# MC21R01_uC_Power.net
KiCad netlist of a schematic drawn in Altium Designer
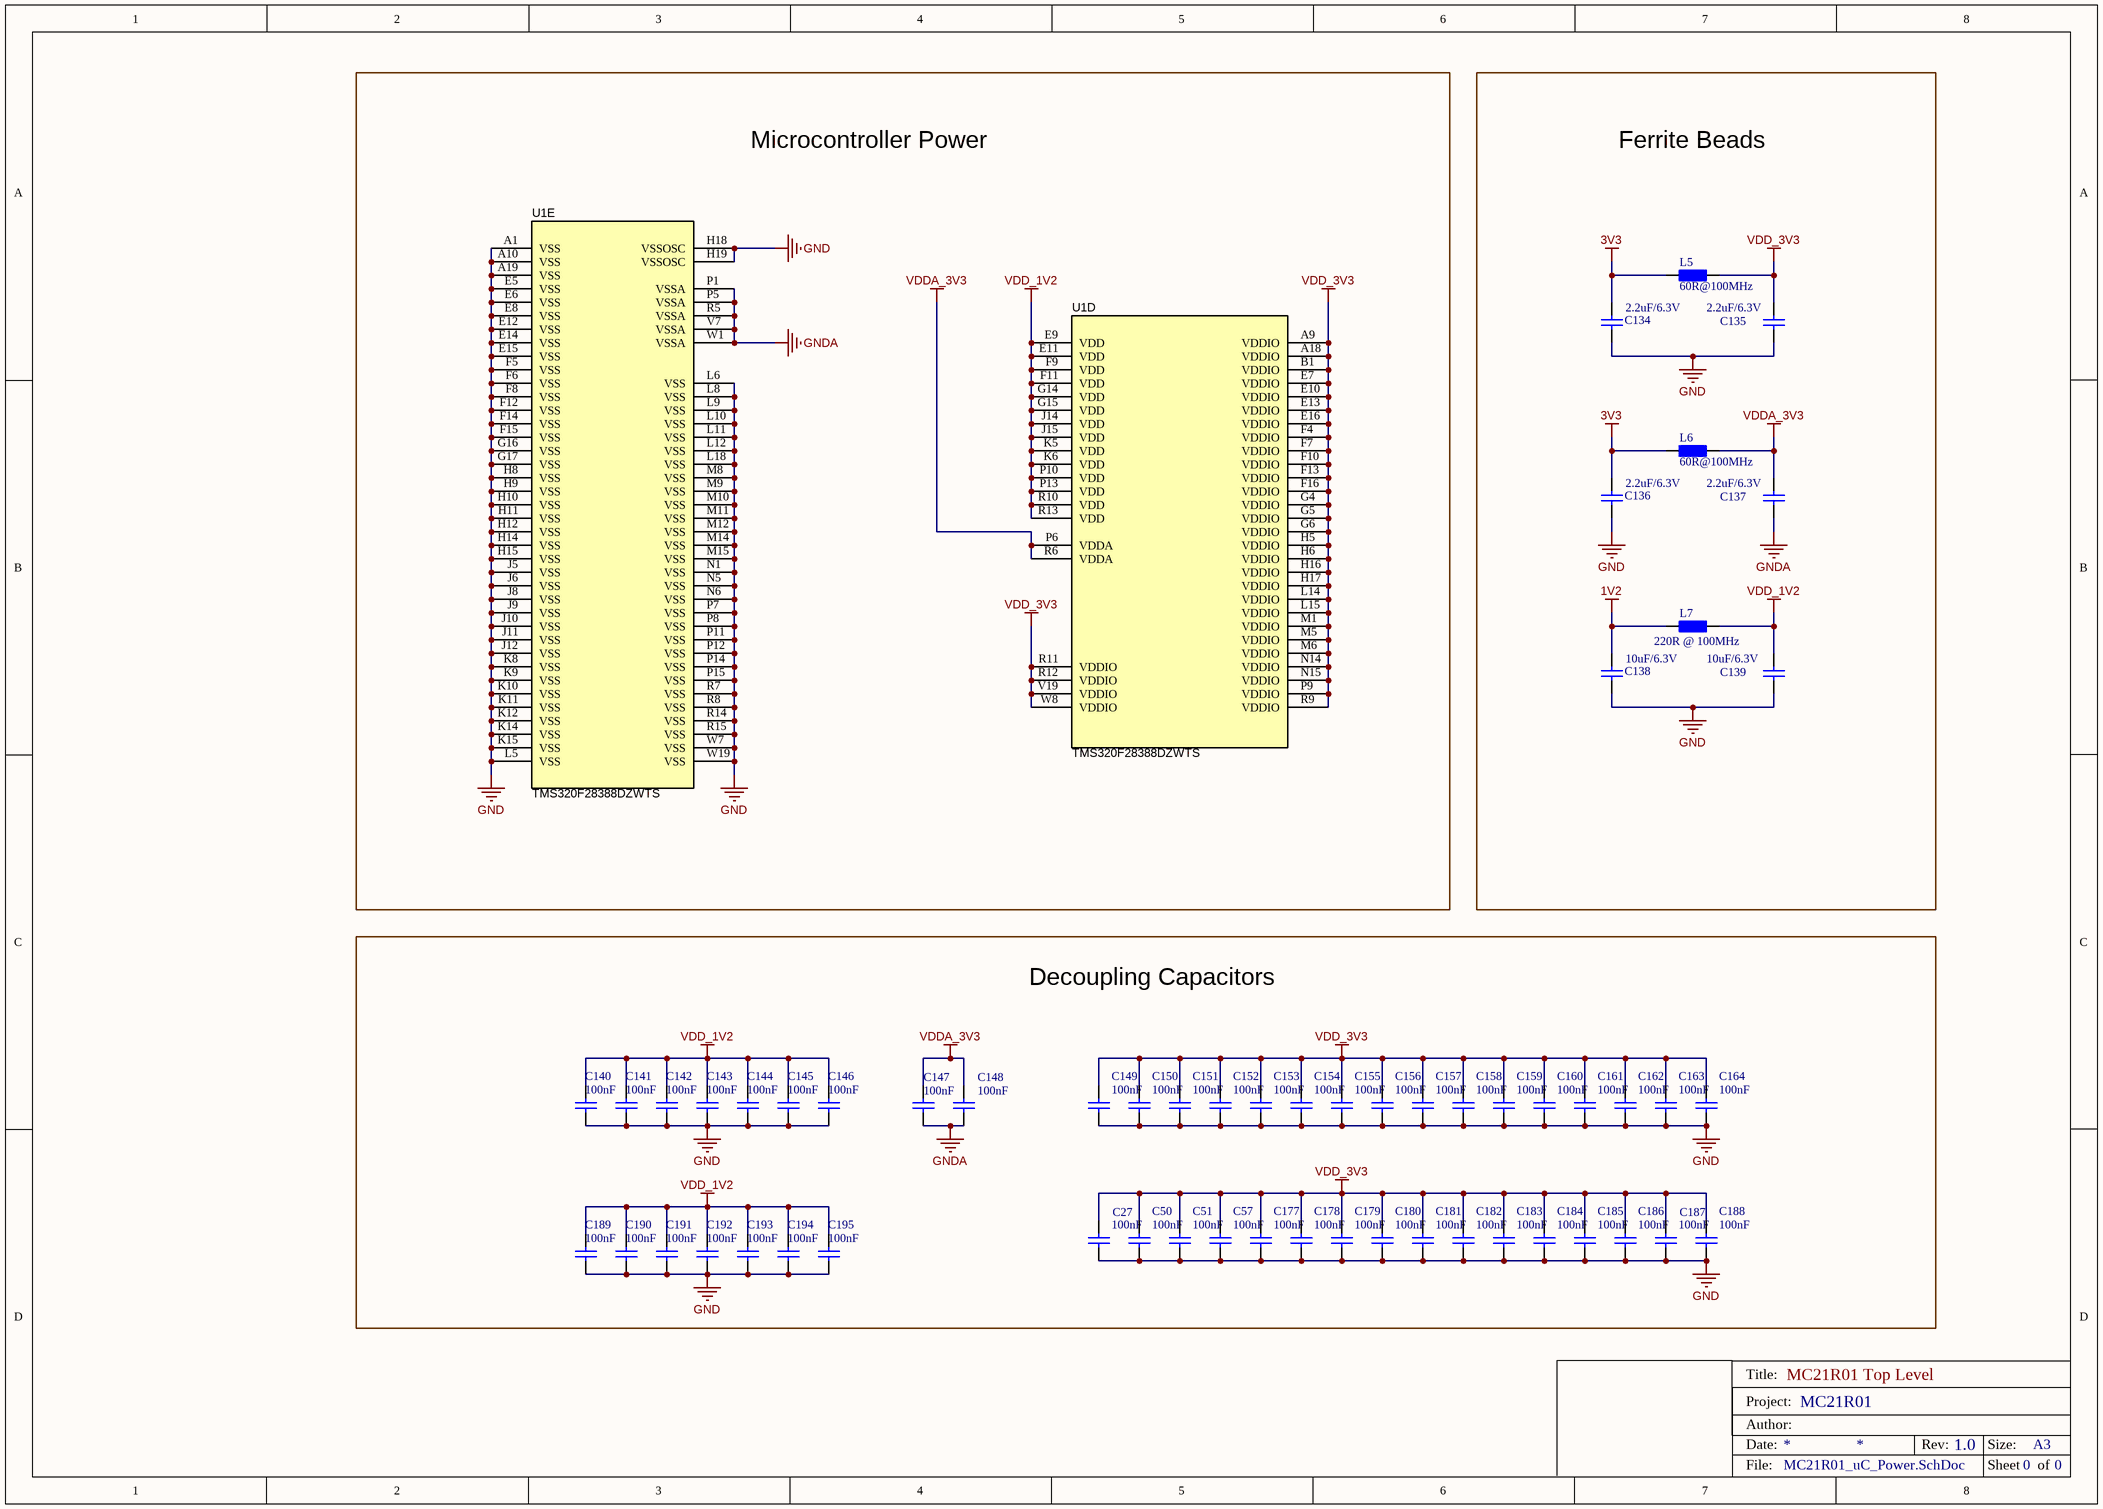
[diagram p0: MC21R01_uC_Power.SchDoc]

(export (version "E")
  (design (tool "Eeschema 10.0.6"))
  (components
    (comp (ref "C27")
      (value "100nF")
      (footprint "CAPC0603X03N")
      (description "100nF/25V 0201 10% Tolerance X6S Multilayer Ceramic Chip Capacitor")
      (fields (field (name "TOLERANCE") "10%") (field (name "Comment") "100nF/25V 0201 10% X6S"))
      (libsource (lib "Wandercraft") (part "STD_CAP_2PIN_NPOL"))
    )
    (comp (ref "C50")
      (value "100nF")
      (footprint "CAPC0603X03N")
      (description "100nF/25V 0201 10% Tolerance X6S Multilayer Ceramic Chip Capacitor")
      (fields (field (name "TOLERANCE") "10%") (field (name "Comment") "100nF/25V 0201 10% X6S"))
      (libsource (lib "Wandercraft") (part "STD_CAP_2PIN_NPOL"))
    )
    (comp (ref "C51")
      (value "100nF")
      (footprint "CAPC0603X03N")
      (description "100nF/25V 0201 10% Tolerance X6S Multilayer Ceramic Chip Capacitor")
      (fields (field (name "TOLERANCE") "10%") (field (name "Comment") "100nF/25V 0201 10% X6S"))
      (libsource (lib "Wandercraft") (part "STD_CAP_2PIN_NPOL"))
    )
    (comp (ref "C57")
      (value "100nF")
      (footprint "CAPC0603X03N")
      (description "100nF/25V 0201 10% Tolerance X6S Multilayer Ceramic Chip Capacitor")
      (fields (field (name "TOLERANCE") "10%") (field (name "Comment") "100nF/25V 0201 10% X6S"))
      (libsource (lib "Wandercraft") (part "STD_CAP_2PIN_NPOL"))
    )
    (comp (ref "C134")
      (value "2.2uF/6.3V")
      (footprint "PAL_Capacitors:0402 SMD Capacitor")
      (description "2.2uF/6.3V 0402 10% Tolerance X5R Multilayer Ceramic Chip Capacitor")
      (fields (field (name "Comment") "2.2uF/6.3V 0402 10% X5R"))
      (libsource (lib "PAL_Capacitors") (part "2.2uF/6.3V 0402 10% X5R_1"))
    )
    (comp (ref "C135")
      (value "2.2uF/6.3V")
      (footprint "PAL_Capacitors:0402 SMD Capacitor")
      (description "2.2uF/6.3V 0402 10% Tolerance X5R Multilayer Ceramic Chip Capacitor")
      (fields (field (name "Comment") "2.2uF/6.3V 0402 10% X5R"))
      (libsource (lib "PAL_Capacitors") (part "2.2uF/6.3V 0402 10% X5R_1"))
    )
    (comp (ref "C136")
      (value "2.2uF/6.3V")
      (footprint "PAL_Capacitors:0402 SMD Capacitor")
      (description "2.2uF/6.3V 0402 10% Tolerance X5R Multilayer Ceramic Chip Capacitor")
      (fields (field (name "Comment") "2.2uF/6.3V 0402 10% X5R"))
      (libsource (lib "PAL_Capacitors") (part "2.2uF/6.3V 0402 10% X5R_1"))
    )
    (comp (ref "C137")
      (value "2.2uF/6.3V")
      (footprint "PAL_Capacitors:0402 SMD Capacitor")
      (description "2.2uF/6.3V 0402 10% Tolerance X5R Multilayer Ceramic Chip Capacitor")
      (fields (field (name "Comment") "2.2uF/6.3V 0402 10% X5R"))
      (libsource (lib "PAL_Capacitors") (part "2.2uF/6.3V 0402 10% X5R_1"))
    )
    (comp (ref "C138")
      (value "10uF/6.3V")
      (footprint "PAL_Capacitors:0402 SMD Capacitor")
      (description "10uF/6.3V 0402 20% Tolerance X5R Multilayer Ceramic Chip Capacitor")
      (fields (field (name "Comment") "10uF/6.3V 0402 20% X5R"))
      (libsource (lib "PAL_Capacitors") (part "10uF/6.3V 0402 20% X5R"))
    )
    (comp (ref "C139")
      (value "10uF/6.3V")
      (footprint "PAL_Capacitors:0402 SMD Capacitor")
      (description "10uF/6.3V 0402 20% Tolerance X5R Multilayer Ceramic Chip Capacitor")
      (fields (field (name "Comment") "10uF/6.3V 0402 20% X5R"))
      (libsource (lib "PAL_Capacitors") (part "10uF/6.3V 0402 20% X5R"))
    )
    (comp (ref "C140")
      (value "100nF")
      (footprint "CAPC0603X03N")
      (description "100nF/25V 0201 10% Tolerance X6S Multilayer Ceramic Chip Capacitor")
      (fields (field (name "TOLERANCE") "10%") (field (name "Comment") "100nF/25V 0201 10% X6S"))
      (libsource (lib "Wandercraft") (part "STD_CAP_2PIN_NPOL"))
    )
    (comp (ref "C141")
      (value "100nF")
      (footprint "CAPC0603X03N")
      (description "100nF/25V 0201 10% Tolerance X6S Multilayer Ceramic Chip Capacitor")
      (fields (field (name "TOLERANCE") "10%") (field (name "Comment") "100nF/25V 0201 10% X6S"))
      (libsource (lib "Wandercraft") (part "STD_CAP_2PIN_NPOL"))
    )
    (comp (ref "C142")
      (value "100nF")
      (footprint "CAPC0603X03N")
      (description "100nF/25V 0201 10% Tolerance X6S Multilayer Ceramic Chip Capacitor")
      (fields (field (name "TOLERANCE") "10%") (field (name "Comment") "100nF/25V 0201 10% X6S"))
      (libsource (lib "Wandercraft") (part "STD_CAP_2PIN_NPOL"))
    )
    (comp (ref "C143")
      (value "100nF")
      (footprint "CAPC0603X03N")
      (description "100nF/25V 0201 10% Tolerance X6S Multilayer Ceramic Chip Capacitor")
      (fields (field (name "TOLERANCE") "10%") (field (name "Comment") "100nF/25V 0201 10% X6S"))
      (libsource (lib "Wandercraft") (part "STD_CAP_2PIN_NPOL"))
    )
    (comp (ref "C144")
      (value "100nF")
      (footprint "CAPC0603X03N")
      (description "100nF/25V 0201 10% Tolerance X6S Multilayer Ceramic Chip Capacitor")
      (fields (field (name "TOLERANCE") "10%") (field (name "Comment") "100nF/25V 0201 10% X6S"))
      (libsource (lib "Wandercraft") (part "STD_CAP_2PIN_NPOL"))
    )
    (comp (ref "C145")
      (value "100nF")
      (footprint "CAPC0603X03N")
      (description "100nF/25V 0201 10% Tolerance X6S Multilayer Ceramic Chip Capacitor")
      (fields (field (name "TOLERANCE") "10%") (field (name "Comment") "100nF/25V 0201 10% X6S"))
      (libsource (lib "Wandercraft") (part "STD_CAP_2PIN_NPOL"))
    )
    (comp (ref "C146")
      (value "100nF")
      (footprint "CAPC0603X03N")
      (description "100nF/25V 0201 10% Tolerance X6S Multilayer Ceramic Chip Capacitor")
      (fields (field (name "TOLERANCE") "10%") (field (name "Comment") "100nF/25V 0201 10% X6S"))
      (libsource (lib "Wandercraft") (part "STD_CAP_2PIN_NPOL"))
    )
    (comp (ref "C147")
      (value "100nF")
      (footprint "CAPC0603X03N")
      (description "100nF/25V 0201 10% Tolerance X6S Multilayer Ceramic Chip Capacitor")
      (fields (field (name "TOLERANCE") "10%") (field (name "Comment") "100nF/25V 0201 10% X6S"))
      (libsource (lib "Wandercraft") (part "STD_CAP_2PIN_NPOL"))
    )
    (comp (ref "C148")
      (value "100nF")
      (footprint "CAPC0603X03N")
      (description "100nF/25V 0201 10% Tolerance X6S Multilayer Ceramic Chip Capacitor")
      (fields (field (name "TOLERANCE") "10%") (field (name "Comment") "100nF/25V 0201 10% X6S"))
      (libsource (lib "Wandercraft") (part "STD_CAP_2PIN_NPOL"))
    )
    (comp (ref "C149")
      (value "100nF")
      (footprint "CAPC0603X03N")
      (description "100nF/25V 0201 10% Tolerance X6S Multilayer Ceramic Chip Capacitor")
      (fields (field (name "TOLERANCE") "10%") (field (name "Comment") "100nF/25V 0201 10% X6S"))
      (libsource (lib "Wandercraft") (part "STD_CAP_2PIN_NPOL"))
    )
    (comp (ref "C150")
      (value "100nF")
      (footprint "CAPC0603X03N")
      (description "100nF/25V 0201 10% Tolerance X6S Multilayer Ceramic Chip Capacitor")
      (fields (field (name "TOLERANCE") "10%") (field (name "Comment") "100nF/25V 0201 10% X6S"))
      (libsource (lib "Wandercraft") (part "STD_CAP_2PIN_NPOL"))
    )
    (comp (ref "C151")
      (value "100nF")
      (footprint "CAPC0603X03N")
      (description "100nF/25V 0201 10% Tolerance X6S Multilayer Ceramic Chip Capacitor")
      (fields (field (name "TOLERANCE") "10%") (field (name "Comment") "100nF/25V 0201 10% X6S"))
      (libsource (lib "Wandercraft") (part "STD_CAP_2PIN_NPOL"))
    )
    (comp (ref "C152")
      (value "100nF")
      (footprint "CAPC0603X03N")
      (description "100nF/25V 0201 10% Tolerance X6S Multilayer Ceramic Chip Capacitor")
      (fields (field (name "TOLERANCE") "10%") (field (name "Comment") "100nF/25V 0201 10% X6S"))
      (libsource (lib "Wandercraft") (part "STD_CAP_2PIN_NPOL"))
    )
    (comp (ref "C153")
      (value "100nF")
      (footprint "CAPC0603X03N")
      (description "100nF/25V 0201 10% Tolerance X6S Multilayer Ceramic Chip Capacitor")
      (fields (field (name "TOLERANCE") "10%") (field (name "Comment") "100nF/25V 0201 10% X6S"))
      (libsource (lib "Wandercraft") (part "STD_CAP_2PIN_NPOL"))
    )
    (comp (ref "C154")
      (value "100nF")
      (footprint "CAPC0603X03N")
      (description "100nF/25V 0201 10% Tolerance X6S Multilayer Ceramic Chip Capacitor")
      (fields (field (name "TOLERANCE") "10%") (field (name "Comment") "100nF/25V 0201 10% X6S"))
      (libsource (lib "Wandercraft") (part "STD_CAP_2PIN_NPOL"))
    )
    (comp (ref "C155")
      (value "100nF")
      (footprint "CAPC0603X03N")
      (description "100nF/25V 0201 10% Tolerance X6S Multilayer Ceramic Chip Capacitor")
      (fields (field (name "TOLERANCE") "10%") (field (name "Comment") "100nF/25V 0201 10% X6S"))
      (libsource (lib "Wandercraft") (part "STD_CAP_2PIN_NPOL"))
    )
    (comp (ref "C156")
      (value "100nF")
      (footprint "CAPC0603X03N")
      (description "100nF/25V 0201 10% Tolerance X6S Multilayer Ceramic Chip Capacitor")
      (fields (field (name "TOLERANCE") "10%") (field (name "Comment") "100nF/25V 0201 10% X6S"))
      (libsource (lib "Wandercraft") (part "STD_CAP_2PIN_NPOL"))
    )
    (comp (ref "C157")
      (value "100nF")
      (footprint "CAPC0603X03N")
      (description "100nF/25V 0201 10% Tolerance X6S Multilayer Ceramic Chip Capacitor")
      (fields (field (name "TOLERANCE") "10%") (field (name "Comment") "100nF/25V 0201 10% X6S"))
      (libsource (lib "Wandercraft") (part "STD_CAP_2PIN_NPOL"))
    )
    (comp (ref "C158")
      (value "100nF")
      (footprint "CAPC0603X03N")
      (description "100nF/25V 0201 10% Tolerance X6S Multilayer Ceramic Chip Capacitor")
      (fields (field (name "TOLERANCE") "10%") (field (name "Comment") "100nF/25V 0201 10% X6S"))
      (libsource (lib "Wandercraft") (part "STD_CAP_2PIN_NPOL"))
    )
    (comp (ref "C159")
      (value "100nF")
      (footprint "CAPC0603X03N")
      (description "100nF/25V 0201 10% Tolerance X6S Multilayer Ceramic Chip Capacitor")
      (fields (field (name "TOLERANCE") "10%") (field (name "Comment") "100nF/25V 0201 10% X6S"))
      (libsource (lib "Wandercraft") (part "STD_CAP_2PIN_NPOL"))
    )
    (comp (ref "C160")
      (value "100nF")
      (footprint "CAPC0603X03N")
      (description "100nF/25V 0201 10% Tolerance X6S Multilayer Ceramic Chip Capacitor")
      (fields (field (name "TOLERANCE") "10%") (field (name "Comment") "100nF/25V 0201 10% X6S"))
      (libsource (lib "Wandercraft") (part "STD_CAP_2PIN_NPOL"))
    )
    (comp (ref "C161")
      (value "100nF")
      (footprint "CAPC0603X03N")
      (description "100nF/25V 0201 10% Tolerance X6S Multilayer Ceramic Chip Capacitor")
      (fields (field (name "TOLERANCE") "10%") (field (name "Comment") "100nF/25V 0201 10% X6S"))
      (libsource (lib "Wandercraft") (part "STD_CAP_2PIN_NPOL"))
    )
    (comp (ref "C162")
      (value "100nF")
      (footprint "CAPC0603X03N")
      (description "100nF/25V 0201 10% Tolerance X6S Multilayer Ceramic Chip Capacitor")
      (fields (field (name "TOLERANCE") "10%") (field (name "Comment") "100nF/25V 0201 10% X6S"))
      (libsource (lib "Wandercraft") (part "STD_CAP_2PIN_NPOL"))
    )
    (comp (ref "C163")
      (value "100nF")
      (footprint "CAPC0603X03N")
      (description "100nF/25V 0201 10% Tolerance X6S Multilayer Ceramic Chip Capacitor")
      (fields (field (name "TOLERANCE") "10%") (field (name "Comment") "100nF/25V 0201 10% X6S"))
      (libsource (lib "Wandercraft") (part "STD_CAP_2PIN_NPOL"))
    )
    (comp (ref "C164")
      (value "100nF")
      (footprint "CAPC0603X03N")
      (description "100nF/25V 0201 10% Tolerance X6S Multilayer Ceramic Chip Capacitor")
      (fields (field (name "TOLERANCE") "10%") (field (name "Comment") "100nF/25V 0201 10% X6S"))
      (libsource (lib "Wandercraft") (part "STD_CAP_2PIN_NPOL"))
    )
    (comp (ref "C177")
      (value "100nF")
      (footprint "CAPC0603X03N")
      (description "100nF/25V 0201 10% Tolerance X6S Multilayer Ceramic Chip Capacitor")
      (fields (field (name "TOLERANCE") "10%") (field (name "Comment") "100nF/25V 0201 10% X6S"))
      (libsource (lib "Wandercraft") (part "STD_CAP_2PIN_NPOL"))
    )
    (comp (ref "C178")
      (value "100nF")
      (footprint "CAPC0603X03N")
      (description "100nF/25V 0201 10% Tolerance X6S Multilayer Ceramic Chip Capacitor")
      (fields (field (name "TOLERANCE") "10%") (field (name "Comment") "100nF/25V 0201 10% X6S"))
      (libsource (lib "Wandercraft") (part "STD_CAP_2PIN_NPOL"))
    )
    (comp (ref "C179")
      (value "100nF")
      (footprint "CAPC0603X03N")
      (description "100nF/25V 0201 10% Tolerance X6S Multilayer Ceramic Chip Capacitor")
      (fields (field (name "TOLERANCE") "10%") (field (name "Comment") "100nF/25V 0201 10% X6S"))
      (libsource (lib "Wandercraft") (part "STD_CAP_2PIN_NPOL"))
    )
    (comp (ref "C180")
      (value "100nF")
      (footprint "CAPC0603X03N")
      (description "100nF/25V 0201 10% Tolerance X6S Multilayer Ceramic Chip Capacitor")
      (fields (field (name "TOLERANCE") "10%") (field (name "Comment") "100nF/25V 0201 10% X6S"))
      (libsource (lib "Wandercraft") (part "STD_CAP_2PIN_NPOL"))
    )
    (comp (ref "C181")
      (value "100nF")
      (footprint "CAPC0603X03N")
      (description "100nF/25V 0201 10% Tolerance X6S Multilayer Ceramic Chip Capacitor")
      (fields (field (name "TOLERANCE") "10%") (field (name "Comment") "100nF/25V 0201 10% X6S"))
      (libsource (lib "Wandercraft") (part "STD_CAP_2PIN_NPOL"))
    )
    (comp (ref "C182")
      (value "100nF")
      (footprint "CAPC0603X03N")
      (description "100nF/25V 0201 10% Tolerance X6S Multilayer Ceramic Chip Capacitor")
      (fields (field (name "TOLERANCE") "10%") (field (name "Comment") "100nF/25V 0201 10% X6S"))
      (libsource (lib "Wandercraft") (part "STD_CAP_2PIN_NPOL"))
    )
    (comp (ref "C183")
      (value "100nF")
      (footprint "CAPC0603X03N")
      (description "100nF/25V 0201 10% Tolerance X6S Multilayer Ceramic Chip Capacitor")
      (fields (field (name "TOLERANCE") "10%") (field (name "Comment") "100nF/25V 0201 10% X6S"))
      (libsource (lib "Wandercraft") (part "STD_CAP_2PIN_NPOL"))
    )
    (comp (ref "C184")
      (value "100nF")
      (footprint "CAPC0603X03N")
      (description "100nF/25V 0201 10% Tolerance X6S Multilayer Ceramic Chip Capacitor")
      (fields (field (name "TOLERANCE") "10%") (field (name "Comment") "100nF/25V 0201 10% X6S"))
      (libsource (lib "Wandercraft") (part "STD_CAP_2PIN_NPOL"))
    )
    (comp (ref "C185")
      (value "100nF")
      (footprint "CAPC0603X03N")
      (description "100nF/25V 0201 10% Tolerance X6S Multilayer Ceramic Chip Capacitor")
      (fields (field (name "TOLERANCE") "10%") (field (name "Comment") "100nF/25V 0201 10% X6S"))
      (libsource (lib "Wandercraft") (part "STD_CAP_2PIN_NPOL"))
    )
    (comp (ref "C186")
      (value "100nF")
      (footprint "CAPC0603X03N")
      (description "100nF/25V 0201 10% Tolerance X6S Multilayer Ceramic Chip Capacitor")
      (fields (field (name "TOLERANCE") "10%") (field (name "Comment") "100nF/25V 0201 10% X6S"))
      (libsource (lib "Wandercraft") (part "STD_CAP_2PIN_NPOL"))
    )
    (comp (ref "C187")
      (value "100nF")
      (footprint "CAPC0603X03N")
      (description "100nF/25V 0201 10% Tolerance X6S Multilayer Ceramic Chip Capacitor")
      (fields (field (name "TOLERANCE") "10%") (field (name "Comment") "100nF/25V 0201 10% X6S"))
      (libsource (lib "Wandercraft") (part "STD_CAP_2PIN_NPOL"))
    )
    (comp (ref "C188")
      (value "100nF")
      (footprint "CAPC0603X03N")
      (description "100nF/25V 0201 10% Tolerance X6S Multilayer Ceramic Chip Capacitor")
      (fields (field (name "TOLERANCE") "10%") (field (name "Comment") "100nF/25V 0201 10% X6S"))
      (libsource (lib "Wandercraft") (part "STD_CAP_2PIN_NPOL"))
    )
    (comp (ref "C189")
      (value "100nF")
      (footprint "CAPC0603X03N")
      (description "100nF/25V 0201 10% Tolerance X6S Multilayer Ceramic Chip Capacitor")
      (fields (field (name "TOLERANCE") "10%") (field (name "Comment") "100nF/25V 0201 10% X6S"))
      (libsource (lib "Wandercraft") (part "STD_CAP_2PIN_NPOL"))
    )
    (comp (ref "C190")
      (value "100nF")
      (footprint "CAPC0603X03N")
      (description "100nF/25V 0201 10% Tolerance X6S Multilayer Ceramic Chip Capacitor")
      (fields (field (name "TOLERANCE") "10%") (field (name "Comment") "100nF/25V 0201 10% X6S"))
      (libsource (lib "Wandercraft") (part "STD_CAP_2PIN_NPOL"))
    )
    (comp (ref "C191")
      (value "100nF")
      (footprint "CAPC0603X03N")
      (description "100nF/25V 0201 10% Tolerance X6S Multilayer Ceramic Chip Capacitor")
      (fields (field (name "TOLERANCE") "10%") (field (name "Comment") "100nF/25V 0201 10% X6S"))
      (libsource (lib "Wandercraft") (part "STD_CAP_2PIN_NPOL"))
    )
    (comp (ref "C192")
      (value "100nF")
      (footprint "CAPC0603X03N")
      (description "100nF/25V 0201 10% Tolerance X6S Multilayer Ceramic Chip Capacitor")
      (fields (field (name "TOLERANCE") "10%") (field (name "Comment") "100nF/25V 0201 10% X6S"))
      (libsource (lib "Wandercraft") (part "STD_CAP_2PIN_NPOL"))
    )
    (comp (ref "C193")
      (value "100nF")
      (footprint "CAPC0603X03N")
      (description "100nF/25V 0201 10% Tolerance X6S Multilayer Ceramic Chip Capacitor")
      (fields (field (name "TOLERANCE") "10%") (field (name "Comment") "100nF/25V 0201 10% X6S"))
      (libsource (lib "Wandercraft") (part "STD_CAP_2PIN_NPOL"))
    )
    (comp (ref "C194")
      (value "100nF")
      (footprint "CAPC0603X03N")
      (description "100nF/25V 0201 10% Tolerance X6S Multilayer Ceramic Chip Capacitor")
      (fields (field (name "TOLERANCE") "10%") (field (name "Comment") "100nF/25V 0201 10% X6S"))
      (libsource (lib "Wandercraft") (part "STD_CAP_2PIN_NPOL"))
    )
    (comp (ref "C195")
      (value "100nF")
      (footprint "CAPC0603X03N")
      (description "100nF/25V 0201 10% Tolerance X6S Multilayer Ceramic Chip Capacitor")
      (fields (field (name "TOLERANCE") "10%") (field (name "Comment") "100nF/25V 0201 10% X6S"))
      (libsource (lib "Wandercraft") (part "STD_CAP_2PIN_NPOL"))
    )
    (comp (ref "L5")
      (value "60R@100MHz")
      (footprint "PAL_Inductors:0603 SMD inductor")
      (description "Ferrite Bead, 60 ohm, 0603 [1608 Metric], 3 A, 0.04 ohm, ± 25%")
      (fields (field (name "MPN") "742792602") (field (name "MF") "Wurth Electronik"))
      (libsource (lib "PAL_Inductors") (part "FB, 60 ohm, 0603 [1608 Metric], 3 A, 0.04 ohm, ± 25%"))
    )
    (comp (ref "L6")
      (value "60R@100MHz")
      (footprint "PAL_Inductors:0603 SMD inductor")
      (description "Ferrite Bead, 60 ohm, 0603 [1608 Metric], 3 A, 0.04 ohm, ± 25%")
      (fields (field (name "MPN") "742792602") (field (name "MF") "Wurth Electronik"))
      (libsource (lib "PAL_Inductors") (part "FB, 60 ohm, 0603 [1608 Metric], 3 A, 0.04 ohm, ± 25%"))
    )
    (comp (ref "L7")
      (value "220R @ 100MHz")
      (footprint "PAL_Inductors:0603 SMD inductor")
      (description "Ferrite Bead, 220 ohm, 0603 [1608 Metric], 2 A, 0.05 ohm, ± 25%")
      (fields (field (name "MPN") "BLM18EG221SN1D") (field (name "MF") "MURATA"))
      (libsource (lib "PAL_Inductors") (part "FB, 220 ohm, 0603 [1608 Metric], 2 A, 0.05 ohm, ± 25%"))
    )
    (comp (ref "U1")
      (value "TMS320F28388DZWTS")
      (footprint "ZWT0337A")
      (description "TMS320F28388DZWTS, ZWT0337A (NFBGA-337)")
      (fields
        (field (name "MANUFACTURER") "Texas Instruments")
        (field (name "PARTNUMBER") "TMS320F28388DZWTS")
      )
      (libsource (lib "PAL_devices") (part "TMS320F28388"))
    )
  )
  (nets
    (net (code "1") (name "1V2") (class "Default")
      (node (ref "C138") (pin "1") (pinfunction "1_1") (pintype "passive"))
      (node (ref "L7") (pin "2") (pinfunction "2_2") (pintype "passive"))
    )
    (net (code "2") (name "3V3") (class "Default")
      (node (ref "C134") (pin "1") (pinfunction "1_1") (pintype "passive"))
      (node (ref "C136") (pin "1") (pinfunction "1_1") (pintype "passive"))
      (node (ref "L5") (pin "2") (pinfunction "2_2") (pintype "passive"))
      (node (ref "L6") (pin "2") (pinfunction "2_2") (pintype "passive"))
    )
    (net (code "3") (name "GND") (class "Default")
      (node (ref "C134") (pin "2") (pinfunction "2_2") (pintype "passive"))
      (node (ref "C135") (pin "2") (pinfunction "2_2") (pintype "passive"))
      (node (ref "C136") (pin "2") (pinfunction "2_2") (pintype "passive"))
      (node (ref "C138") (pin "2") (pinfunction "2_2") (pintype "passive"))
      (node (ref "C139") (pin "2") (pinfunction "2_2") (pintype "passive"))
      (node (ref "C140") (pin "1") (pinfunction "1_1") (pintype "passive"))
      (node (ref "C141") (pin "1") (pinfunction "1_1") (pintype "passive"))
      (node (ref "C142") (pin "1") (pinfunction "1_1") (pintype "passive"))
      (node (ref "C143") (pin "1") (pinfunction "1_1") (pintype "passive"))
      (node (ref "C144") (pin "1") (pinfunction "1_1") (pintype "passive"))
      (node (ref "C145") (pin "1") (pinfunction "1_1") (pintype "passive"))
      (node (ref "C146") (pin "1") (pinfunction "1_1") (pintype "passive"))
      (node (ref "C149") (pin "1") (pinfunction "1_1") (pintype "passive"))
      (node (ref "C150") (pin "1") (pinfunction "1_1") (pintype "passive"))
      (node (ref "C151") (pin "1") (pinfunction "1_1") (pintype "passive"))
      (node (ref "C152") (pin "1") (pinfunction "1_1") (pintype "passive"))
      (node (ref "C153") (pin "1") (pinfunction "1_1") (pintype "passive"))
      (node (ref "C154") (pin "1") (pinfunction "1_1") (pintype "passive"))
      (node (ref "C155") (pin "1") (pinfunction "1_1") (pintype "passive"))
      (node (ref "C156") (pin "1") (pinfunction "1_1") (pintype "passive"))
      (node (ref "C157") (pin "1") (pinfunction "1_1") (pintype "passive"))
      (node (ref "C158") (pin "1") (pinfunction "1_1") (pintype "passive"))
      (node (ref "C159") (pin "1") (pinfunction "1_1") (pintype "passive"))
      (node (ref "C160") (pin "1") (pinfunction "1_1") (pintype "passive"))
      (node (ref "C161") (pin "1") (pinfunction "1_1") (pintype "passive"))
      (node (ref "C162") (pin "1") (pinfunction "1_1") (pintype "passive"))
      (node (ref "C163") (pin "1") (pinfunction "1_1") (pintype "passive"))
      (node (ref "C164") (pin "1") (pinfunction "1_1") (pintype "passive"))
      (node (ref "C177") (pin "1") (pinfunction "1_1") (pintype "passive"))
      (node (ref "C178") (pin "1") (pinfunction "1_1") (pintype "passive"))
      (node (ref "C179") (pin "1") (pinfunction "1_1") (pintype "passive"))
      (node (ref "C180") (pin "1") (pinfunction "1_1") (pintype "passive"))
      (node (ref "C181") (pin "1") (pinfunction "1_1") (pintype "passive"))
      (node (ref "C182") (pin "1") (pinfunction "1_1") (pintype "passive"))
      (node (ref "C183") (pin "1") (pinfunction "1_1") (pintype "passive"))
      (node (ref "C184") (pin "1") (pinfunction "1_1") (pintype "passive"))
      (node (ref "C185") (pin "1") (pinfunction "1_1") (pintype "passive"))
      (node (ref "C186") (pin "1") (pinfunction "1_1") (pintype "passive"))
      (node (ref "C187") (pin "1") (pinfunction "1_1") (pintype "passive"))
      (node (ref "C188") (pin "1") (pinfunction "1_1") (pintype "passive"))
      (node (ref "C189") (pin "1") (pinfunction "1_1") (pintype "passive"))
      (node (ref "C190") (pin "1") (pinfunction "1_1") (pintype "passive"))
      (node (ref "C191") (pin "1") (pinfunction "1_1") (pintype "passive"))
      (node (ref "C192") (pin "1") (pinfunction "1_1") (pintype "passive"))
      (node (ref "C193") (pin "1") (pinfunction "1_1") (pintype "passive"))
      (node (ref "C194") (pin "1") (pinfunction "1_1") (pintype "passive"))
      (node (ref "C195") (pin "1") (pinfunction "1_1") (pintype "passive"))
      (node (ref "C27") (pin "1") (pinfunction "1_1") (pintype "passive"))
      (node (ref "C50") (pin "1") (pinfunction "1_1") (pintype "passive"))
      (node (ref "C51") (pin "1") (pinfunction "1_1") (pintype "passive"))
      (node (ref "C57") (pin "1") (pinfunction "1_1") (pintype "passive"))
      (node (ref "U1") (pin "A1") (pinfunction "VSS_A1") (pintype "power_in"))
      (node (ref "U1") (pin "A10") (pinfunction "VSS_A10") (pintype "power_in"))
      (node (ref "U1") (pin "A19") (pinfunction "VSS_A19") (pintype "power_in"))
      (node (ref "U1") (pin "E12") (pinfunction "VSS_E12") (pintype "power_in"))
      (node (ref "U1") (pin "E14") (pinfunction "VSS_E14") (pintype "power_in"))
      (node (ref "U1") (pin "E15") (pinfunction "VSS_E15") (pintype "power_in"))
      (node (ref "U1") (pin "E5") (pinfunction "VSS_E5") (pintype "power_in"))
      (node (ref "U1") (pin "E6") (pinfunction "VSS_E6") (pintype "power_in"))
      (node (ref "U1") (pin "E8") (pinfunction "VSS_E8") (pintype "power_in"))
      (node (ref "U1") (pin "F12") (pinfunction "VSS_F12") (pintype "power_in"))
      (node (ref "U1") (pin "F14") (pinfunction "VSS_F14") (pintype "power_in"))
      (node (ref "U1") (pin "F15") (pinfunction "VSS_F15") (pintype "power_in"))
      (node (ref "U1") (pin "F5") (pinfunction "VSS_F5") (pintype "power_in"))
      (node (ref "U1") (pin "F6") (pinfunction "VSS_F6") (pintype "power_in"))
      (node (ref "U1") (pin "F8") (pinfunction "VSS_F8") (pintype "power_in"))
      (node (ref "U1") (pin "G16") (pinfunction "VSS_G16") (pintype "power_in"))
      (node (ref "U1") (pin "G17") (pinfunction "VSS_G17") (pintype "power_in"))
      (node (ref "U1") (pin "H10") (pinfunction "VSS_H10") (pintype "power_in"))
      (node (ref "U1") (pin "H11") (pinfunction "VSS_H11") (pintype "power_in"))
      (node (ref "U1") (pin "H12") (pinfunction "VSS_H12") (pintype "power_in"))
      (node (ref "U1") (pin "H14") (pinfunction "VSS_H14") (pintype "power_in"))
      (node (ref "U1") (pin "H15") (pinfunction "VSS_H15") (pintype "power_in"))
      (node (ref "U1") (pin "H18") (pinfunction "VSSOSC_H18") (pintype "power_in"))
      (node (ref "U1") (pin "H19") (pinfunction "VSSOSC_H19") (pintype "power_in"))
      (node (ref "U1") (pin "H8") (pinfunction "VSS_H8") (pintype "power_in"))
      (node (ref "U1") (pin "H9") (pinfunction "VSS_H9") (pintype "power_in"))
      (node (ref "U1") (pin "J10") (pinfunction "VSS_J10") (pintype "power_in"))
      (node (ref "U1") (pin "J11") (pinfunction "VSS_J11") (pintype "power_in"))
      (node (ref "U1") (pin "J12") (pinfunction "VSS_J12") (pintype "power_in"))
      (node (ref "U1") (pin "J5") (pinfunction "VSS_J5") (pintype "power_in"))
      (node (ref "U1") (pin "J6") (pinfunction "VSS_J6") (pintype "power_in"))
      (node (ref "U1") (pin "J8") (pinfunction "VSS_J8") (pintype "power_in"))
      (node (ref "U1") (pin "J9") (pinfunction "VSS_J9") (pintype "power_in"))
      (node (ref "U1") (pin "K10") (pinfunction "VSS_K10") (pintype "power_in"))
      (node (ref "U1") (pin "K11") (pinfunction "VSS_K11") (pintype "power_in"))
      (node (ref "U1") (pin "K12") (pinfunction "VSS_K12") (pintype "power_in"))
      (node (ref "U1") (pin "K14") (pinfunction "VSS_K14") (pintype "power_in"))
      (node (ref "U1") (pin "K15") (pinfunction "VSS_K15") (pintype "power_in"))
      (node (ref "U1") (pin "K8") (pinfunction "VSS_K8") (pintype "power_in"))
      (node (ref "U1") (pin "K9") (pinfunction "VSS_K9") (pintype "power_in"))
      (node (ref "U1") (pin "L10") (pinfunction "VSS_L10") (pintype "power_in"))
      (node (ref "U1") (pin "L11") (pinfunction "VSS_L11") (pintype "power_in"))
      (node (ref "U1") (pin "L12") (pinfunction "VSS_L12") (pintype "power_in"))
      (node (ref "U1") (pin "L18") (pinfunction "VSS_L18") (pintype "power_in"))
      (node (ref "U1") (pin "L5") (pinfunction "VSS_L5") (pintype "power_in"))
      (node (ref "U1") (pin "L6") (pinfunction "VSS_L6") (pintype "power_in"))
      (node (ref "U1") (pin "L8") (pinfunction "VSS_L8") (pintype "power_in"))
      (node (ref "U1") (pin "L9") (pinfunction "VSS_L9") (pintype "power_in"))
      (node (ref "U1") (pin "M10") (pinfunction "VSS_M10") (pintype "power_in"))
      (node (ref "U1") (pin "M11") (pinfunction "VSS_M11") (pintype "power_in"))
      (node (ref "U1") (pin "M12") (pinfunction "VSS_M12") (pintype "power_in"))
      (node (ref "U1") (pin "M14") (pinfunction "VSS_M14") (pintype "power_in"))
      (node (ref "U1") (pin "M15") (pinfunction "VSS_M15") (pintype "power_in"))
      (node (ref "U1") (pin "M8") (pinfunction "VSS_M8") (pintype "power_in"))
      (node (ref "U1") (pin "M9") (pinfunction "VSS_M9") (pintype "power_in"))
      (node (ref "U1") (pin "N1") (pinfunction "VSS_N1") (pintype "power_in"))
      (node (ref "U1") (pin "N5") (pinfunction "VSS_N5") (pintype "power_in"))
      (node (ref "U1") (pin "N6") (pinfunction "VSS_N6") (pintype "power_in"))
      (node (ref "U1") (pin "P11") (pinfunction "VSS_P11") (pintype "power_in"))
      (node (ref "U1") (pin "P12") (pinfunction "VSS_P12") (pintype "power_in"))
      (node (ref "U1") (pin "P14") (pinfunction "VSS_P14") (pintype "power_in"))
      (node (ref "U1") (pin "P15") (pinfunction "VSS_P15") (pintype "power_in"))
      (node (ref "U1") (pin "P7") (pinfunction "VSS_P7") (pintype "power_in"))
      (node (ref "U1") (pin "P8") (pinfunction "VSS_P8") (pintype "power_in"))
      (node (ref "U1") (pin "R14") (pinfunction "VSS_R14") (pintype "power_in"))
      (node (ref "U1") (pin "R15") (pinfunction "VSS_R15") (pintype "power_in"))
      (node (ref "U1") (pin "R7") (pinfunction "VSS_R7") (pintype "power_in"))
      (node (ref "U1") (pin "R8") (pinfunction "VSS_R8") (pintype "power_in"))
      (node (ref "U1") (pin "W19") (pinfunction "VSS_W19") (pintype "power_in"))
      (node (ref "U1") (pin "W7") (pinfunction "VSS_W7") (pintype "power_in"))
    )
    (net (code "4") (name "GNDA") (class "Default")
      (node (ref "C137") (pin "2") (pinfunction "2_2") (pintype "passive"))
      (node (ref "C147") (pin "1") (pinfunction "1_1") (pintype "passive"))
      (node (ref "C148") (pin "1") (pinfunction "1_1") (pintype "passive"))
      (node (ref "U1") (pin "P1") (pinfunction "VSSA_P1") (pintype "power_in"))
      (node (ref "U1") (pin "P5") (pinfunction "VSSA_P5") (pintype "power_in"))
      (node (ref "U1") (pin "R5") (pinfunction "VSSA_R5") (pintype "power_in"))
      (node (ref "U1") (pin "V7") (pinfunction "VSSA_V7") (pintype "power_in"))
      (node (ref "U1") (pin "W1") (pinfunction "VSSA_W1") (pintype "power_in"))
    )
    (net (code "5") (name "VDDA_3V3") (class "Default")
      (node (ref "C137") (pin "1") (pinfunction "1_1") (pintype "passive"))
      (node (ref "C147") (pin "2") (pinfunction "2_2") (pintype "passive"))
      (node (ref "C148") (pin "2") (pinfunction "2_2") (pintype "passive"))
      (node (ref "L6") (pin "1") (pinfunction "1_1") (pintype "passive"))
      (node (ref "U1") (pin "P6") (pinfunction "VDDA_P6") (pintype "power_in"))
      (node (ref "U1") (pin "R6") (pinfunction "VDDA_R6") (pintype "power_in"))
    )
    (net (code "6") (name "VDD_1V2") (class "Default")
      (node (ref "C139") (pin "1") (pinfunction "1_1") (pintype "passive"))
      (node (ref "C140") (pin "2") (pinfunction "2_2") (pintype "passive"))
      (node (ref "C141") (pin "2") (pinfunction "2_2") (pintype "passive"))
      (node (ref "C142") (pin "2") (pinfunction "2_2") (pintype "passive"))
      (node (ref "C143") (pin "2") (pinfunction "2_2") (pintype "passive"))
      (node (ref "C144") (pin "2") (pinfunction "2_2") (pintype "passive"))
      (node (ref "C145") (pin "2") (pinfunction "2_2") (pintype "passive"))
      (node (ref "C146") (pin "2") (pinfunction "2_2") (pintype "passive"))
      (node (ref "C189") (pin "2") (pinfunction "2_2") (pintype "passive"))
      (node (ref "C190") (pin "2") (pinfunction "2_2") (pintype "passive"))
      (node (ref "C191") (pin "2") (pinfunction "2_2") (pintype "passive"))
      (node (ref "C192") (pin "2") (pinfunction "2_2") (pintype "passive"))
      (node (ref "C193") (pin "2") (pinfunction "2_2") (pintype "passive"))
      (node (ref "C194") (pin "2") (pinfunction "2_2") (pintype "passive"))
      (node (ref "C195") (pin "2") (pinfunction "2_2") (pintype "passive"))
      (node (ref "L7") (pin "1") (pinfunction "1_1") (pintype "passive"))
      (node (ref "U1") (pin "E11") (pinfunction "VDD_E11") (pintype "power_in"))
      (node (ref "U1") (pin "E9") (pinfunction "VDD_E9") (pintype "power_in"))
      (node (ref "U1") (pin "F11") (pinfunction "VDD_F11") (pintype "power_in"))
      (node (ref "U1") (pin "F9") (pinfunction "VDD_F9") (pintype "power_in"))
      (node (ref "U1") (pin "G14") (pinfunction "VDD_G14") (pintype "power_in"))
      (node (ref "U1") (pin "G15") (pinfunction "VDD_G15") (pintype "power_in"))
      (node (ref "U1") (pin "J14") (pinfunction "VDD_J14") (pintype "power_in"))
      (node (ref "U1") (pin "J15") (pinfunction "VDD_J15") (pintype "power_in"))
      (node (ref "U1") (pin "K5") (pinfunction "VDD_K5") (pintype "power_in"))
      (node (ref "U1") (pin "K6") (pinfunction "VDD_K6") (pintype "power_in"))
      (node (ref "U1") (pin "P10") (pinfunction "VDD_P10") (pintype "power_in"))
      (node (ref "U1") (pin "P13") (pinfunction "VDD_P13") (pintype "power_in"))
      (node (ref "U1") (pin "R10") (pinfunction "VDD_R10") (pintype "power_in"))
      (node (ref "U1") (pin "R13") (pinfunction "VDD_R13") (pintype "power_in"))
    )
    (net (code "7") (name "VDD_3V3") (class "Default")
      (node (ref "C135") (pin "1") (pinfunction "1_1") (pintype "passive"))
      (node (ref "C149") (pin "2") (pinfunction "2_2") (pintype "passive"))
      (node (ref "C150") (pin "2") (pinfunction "2_2") (pintype "passive"))
      (node (ref "C151") (pin "2") (pinfunction "2_2") (pintype "passive"))
      (node (ref "C152") (pin "2") (pinfunction "2_2") (pintype "passive"))
      (node (ref "C153") (pin "2") (pinfunction "2_2") (pintype "passive"))
      (node (ref "C154") (pin "2") (pinfunction "2_2") (pintype "passive"))
      (node (ref "C155") (pin "2") (pinfunction "2_2") (pintype "passive"))
      (node (ref "C156") (pin "2") (pinfunction "2_2") (pintype "passive"))
      (node (ref "C157") (pin "2") (pinfunction "2_2") (pintype "passive"))
      (node (ref "C158") (pin "2") (pinfunction "2_2") (pintype "passive"))
      (node (ref "C159") (pin "2") (pinfunction "2_2") (pintype "passive"))
      (node (ref "C160") (pin "2") (pinfunction "2_2") (pintype "passive"))
      (node (ref "C161") (pin "2") (pinfunction "2_2") (pintype "passive"))
      (node (ref "C162") (pin "2") (pinfunction "2_2") (pintype "passive"))
      (node (ref "C163") (pin "2") (pinfunction "2_2") (pintype "passive"))
      (node (ref "C164") (pin "2") (pinfunction "2_2") (pintype "passive"))
      (node (ref "C177") (pin "2") (pinfunction "2_2") (pintype "passive"))
      (node (ref "C178") (pin "2") (pinfunction "2_2") (pintype "passive"))
      (node (ref "C179") (pin "2") (pinfunction "2_2") (pintype "passive"))
      (node (ref "C180") (pin "2") (pinfunction "2_2") (pintype "passive"))
      (node (ref "C181") (pin "2") (pinfunction "2_2") (pintype "passive"))
      (node (ref "C182") (pin "2") (pinfunction "2_2") (pintype "passive"))
      (node (ref "C183") (pin "2") (pinfunction "2_2") (pintype "passive"))
      (node (ref "C184") (pin "2") (pinfunction "2_2") (pintype "passive"))
      (node (ref "C185") (pin "2") (pinfunction "2_2") (pintype "passive"))
      (node (ref "C186") (pin "2") (pinfunction "2_2") (pintype "passive"))
      (node (ref "C187") (pin "2") (pinfunction "2_2") (pintype "passive"))
      (node (ref "C188") (pin "2") (pinfunction "2_2") (pintype "passive"))
      (node (ref "C27") (pin "2") (pinfunction "2_2") (pintype "passive"))
      (node (ref "C50") (pin "2") (pinfunction "2_2") (pintype "passive"))
      (node (ref "C51") (pin "2") (pinfunction "2_2") (pintype "passive"))
      (node (ref "C57") (pin "2") (pinfunction "2_2") (pintype "passive"))
      (node (ref "L5") (pin "1") (pinfunction "1_1") (pintype "passive"))
      (node (ref "U1") (pin "A18") (pinfunction "VDDIO_A18") (pintype "power_in"))
      (node (ref "U1") (pin "A9") (pinfunction "VDDIO_A9") (pintype "power_in"))
      (node (ref "U1") (pin "B1") (pinfunction "VDDIO_B1") (pintype "power_in"))
      (node (ref "U1") (pin "E10") (pinfunction "VDDIO_E10") (pintype "power_in"))
      (node (ref "U1") (pin "E13") (pinfunction "VDDIO_E13") (pintype "power_in"))
      (node (ref "U1") (pin "E16") (pinfunction "VDDIO_E16") (pintype "power_in"))
      (node (ref "U1") (pin "E7") (pinfunction "VDDIO_E7") (pintype "power_in"))
      (node (ref "U1") (pin "F10") (pinfunction "VDDIO_F10") (pintype "power_in"))
      (node (ref "U1") (pin "F13") (pinfunction "VDDIO_F13") (pintype "power_in"))
      (node (ref "U1") (pin "F16") (pinfunction "VDDIO_F16") (pintype "power_in"))
      (node (ref "U1") (pin "F4") (pinfunction "VDDIO_F4") (pintype "power_in"))
      (node (ref "U1") (pin "F7") (pinfunction "VDDIO_F7") (pintype "power_in"))
      (node (ref "U1") (pin "G4") (pinfunction "VDDIO_G4") (pintype "power_in"))
      (node (ref "U1") (pin "G5") (pinfunction "VDDIO_G5") (pintype "power_in"))
      (node (ref "U1") (pin "G6") (pinfunction "VDDIO_G6") (pintype "power_in"))
      (node (ref "U1") (pin "H16") (pinfunction "VDDIO_H16") (pintype "power_in"))
      (node (ref "U1") (pin "H17") (pinfunction "VDDIO_H17") (pintype "power_in"))
      (node (ref "U1") (pin "H5") (pinfunction "VDDIO_H5") (pintype "power_in"))
      (node (ref "U1") (pin "H6") (pinfunction "VDDIO_H6") (pintype "power_in"))
      (node (ref "U1") (pin "L14") (pinfunction "VDDIO_L14") (pintype "power_in"))
      (node (ref "U1") (pin "L15") (pinfunction "VDDIO_L15") (pintype "power_in"))
      (node (ref "U1") (pin "M1") (pinfunction "VDDIO_M1") (pintype "power_in"))
      (node (ref "U1") (pin "M5") (pinfunction "VDDIO_M5") (pintype "power_in"))
      (node (ref "U1") (pin "M6") (pinfunction "VDDIO_M6") (pintype "power_in"))
      (node (ref "U1") (pin "N14") (pinfunction "VDDIO_N14") (pintype "power_in"))
      (node (ref "U1") (pin "N15") (pinfunction "VDDIO_N15") (pintype "power_in"))
      (node (ref "U1") (pin "P9") (pinfunction "VDDIO_P9") (pintype "power_in"))
      (node (ref "U1") (pin "R11") (pinfunction "VDDIO_R11") (pintype "power_in"))
      (node (ref "U1") (pin "R12") (pinfunction "VDDIO_R12") (pintype "power_in"))
      (node (ref "U1") (pin "R9") (pinfunction "VDDIO_R9") (pintype "power_in"))
      (node (ref "U1") (pin "V19") (pinfunction "VDDIO_V19") (pintype "power_in"))
      (node (ref "U1") (pin "W8") (pinfunction "VDDIO_W8") (pintype "power_in"))
    )
  )
)
